# RobotSide.net
KiCad netlist of a schematic drawn in EAGLE
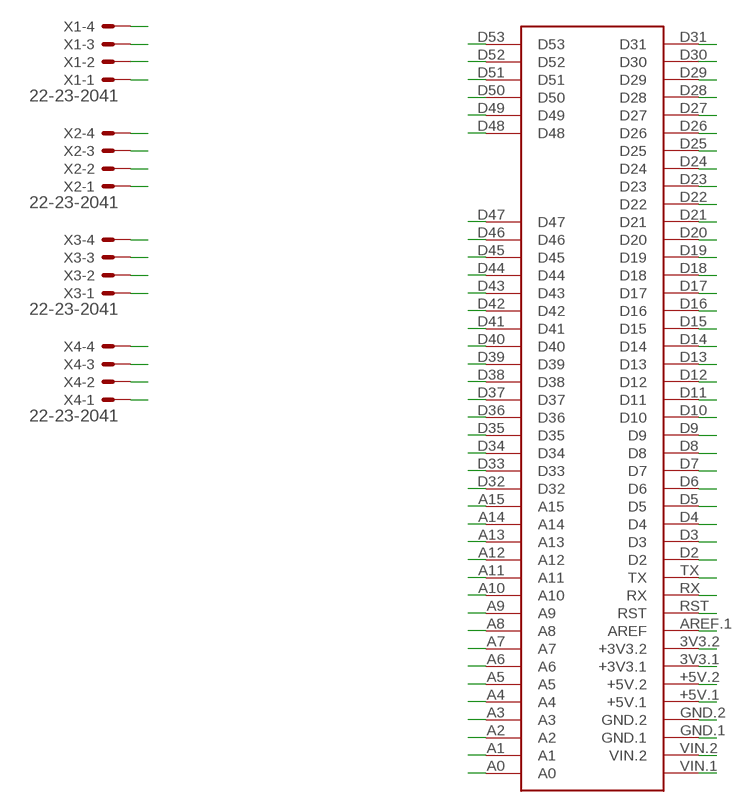
[diagram p0: schematic, sheet 1]
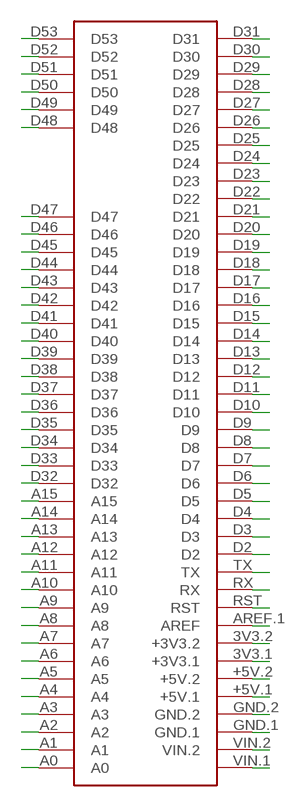
[diagram p1: schematic, sheet 2]

(export (version "E")
  (design (tool "Eeschema 10.0.6"))
  (components
    (comp (ref "U$1")
      (value "MEGA2560_MIKRO")
      (footprint "eagle-import:MEGA2560_MIKRO")
      (libsource (lib "eagle-import") (part "MEGA2560_MIKRO"))
    )
    (comp (ref "X1")
      (value "22-23-2041")
      (footprint "eagle-import:22-23-2041")
      (fields (field (name "MF") "MOLEX"))
      (libsource (lib "eagle-import") (part "22-23-2041"))
    )
    (comp (ref "X2")
      (value "22-23-2041")
      (footprint "eagle-import:22-23-2041")
      (fields (field (name "MF") "MOLEX"))
      (libsource (lib "eagle-import") (part "22-23-2041"))
    )
    (comp (ref "X3")
      (value "22-23-2041")
      (footprint "eagle-import:22-23-2041")
      (fields (field (name "MF") "MOLEX"))
      (libsource (lib "eagle-import") (part "22-23-2041"))
    )
    (comp (ref "X4")
      (value "22-23-2041")
      (footprint "eagle-import:22-23-2041")
      (fields (field (name "MF") "MOLEX"))
      (libsource (lib "eagle-import") (part "22-23-2041"))
    )
    (comp (ref "U$2")
      (value "MEGA2560_MIKRO")
      (footprint "eagle-import:MEGA2560_MIKRO")
      (libsource (lib "eagle-import") (part "MEGA2560_MIKRO"))
    )
  )
  (nets
    (net (code "1") (name "3V3") (class "Default")
      (node (ref "U$1") (pin "3V3.1") (pinfunction "+3V3.1_3V3.1") (pintype "bidirectional"))
      (node (ref "U$1") (pin "3V3.2") (pinfunction "+3V3.2_3V3.2") (pintype "bidirectional"))
    )
    (net (code "2") (name "3V3_A") (class "Default")
      (node (ref "U$2") (pin "3V3.1") (pinfunction "+3V3.1_3V3.1") (pintype "bidirectional"))
      (node (ref "U$2") (pin "3V3.2") (pinfunction "+3V3.2_3V3.2") (pintype "bidirectional"))
    )
    (net (code "3") (name "5V") (class "Default")
      (node (ref "U$1") (pin "+5V.1") (pinfunction "+5V.1_+5V.1") (pintype "bidirectional"))
      (node (ref "U$1") (pin "+5V.2") (pinfunction "+5V.2_+5V.2") (pintype "bidirectional"))
      (node (ref "U$2") (pin "+5V.1") (pinfunction "+5V.1_+5V.1") (pintype "bidirectional"))
      (node (ref "U$2") (pin "+5V.2") (pinfunction "+5V.2_+5V.2") (pintype "bidirectional"))
    )
    (net (code "4") (name "GND") (class "Default")
      (node (ref "U$1") (pin "GND.1") (pinfunction "GND.1_GND.1") (pintype "bidirectional"))
      (node (ref "U$1") (pin "GND.2") (pinfunction "GND.2_GND.2") (pintype "bidirectional"))
      (node (ref "U$2") (pin "GND.1") (pinfunction "GND.1_GND.1") (pintype "bidirectional"))
      (node (ref "U$2") (pin "GND.2") (pinfunction "GND.2_GND.2") (pintype "bidirectional"))
    )
    (net (code "5") (name "VIN") (class "Default")
      (node (ref "U$1") (pin "VIN.1") (pinfunction "VIN.1_VIN.1") (pintype "bidirectional"))
      (node (ref "U$1") (pin "VIN.2") (pinfunction "VIN.2_VIN.2") (pintype "bidirectional"))
    )
    (net (code "6") (name "VIN_A") (class "Default")
      (node (ref "U$2") (pin "VIN.1") (pinfunction "VIN.1_VIN.1") (pintype "bidirectional"))
      (node (ref "U$2") (pin "VIN.2") (pinfunction "VIN.2_VIN.2") (pintype "bidirectional"))
    )
    (net (code "7") (name "unconnected-(U$1-AREF-PadAREF.1)") (class "Default")
      (node (ref "U$1") (pin "AREF.1") (pinfunction "AREF_AREF.1") (pintype "bidirectional"))
    )
    (net (code "8") (name "unconnected-(U$1-PadA0)") (class "Default")
      (node (ref "U$1") (pin "A0") (pinfunction "A0_A0") (pintype "bidirectional"))
    )
    (net (code "9") (name "unconnected-(U$1-PadA1)") (class "Default")
      (node (ref "U$1") (pin "A1") (pinfunction "A1_A1") (pintype "bidirectional"))
    )
    (net (code "10") (name "unconnected-(U$1-PadA2)") (class "Default")
      (node (ref "U$1") (pin "A2") (pinfunction "A2_A2") (pintype "bidirectional"))
    )
    (net (code "11") (name "unconnected-(U$1-PadA3)") (class "Default")
      (node (ref "U$1") (pin "A3") (pinfunction "A3_A3") (pintype "bidirectional"))
    )
    (net (code "12") (name "unconnected-(U$1-PadA4)") (class "Default")
      (node (ref "U$1") (pin "A4") (pinfunction "A4_A4") (pintype "bidirectional"))
    )
    (net (code "13") (name "unconnected-(U$1-PadA5)") (class "Default")
      (node (ref "U$1") (pin "A5") (pinfunction "A5_A5") (pintype "bidirectional"))
    )
    (net (code "14") (name "unconnected-(U$1-PadA6)") (class "Default")
      (node (ref "U$1") (pin "A6") (pinfunction "A6_A6") (pintype "bidirectional"))
    )
    (net (code "15") (name "unconnected-(U$1-PadA7)") (class "Default")
      (node (ref "U$1") (pin "A7") (pinfunction "A7_A7") (pintype "bidirectional"))
    )
    (net (code "16") (name "unconnected-(U$1-PadA8)") (class "Default")
      (node (ref "U$1") (pin "A8") (pinfunction "A8_A8") (pintype "bidirectional"))
    )
    (net (code "17") (name "unconnected-(U$1-PadA9)") (class "Default")
      (node (ref "U$1") (pin "A9") (pinfunction "A9_A9") (pintype "bidirectional"))
    )
    (net (code "18") (name "unconnected-(U$1-PadA10)") (class "Default")
      (node (ref "U$1") (pin "A10") (pinfunction "A10_A10") (pintype "bidirectional"))
    )
    (net (code "19") (name "unconnected-(U$1-PadA11)") (class "Default")
      (node (ref "U$1") (pin "A11") (pinfunction "A11_A11") (pintype "bidirectional"))
    )
    (net (code "20") (name "unconnected-(U$1-PadA12)") (class "Default")
      (node (ref "U$1") (pin "A12") (pinfunction "A12_A12") (pintype "bidirectional"))
    )
    (net (code "21") (name "unconnected-(U$1-PadA13)") (class "Default")
      (node (ref "U$1") (pin "A13") (pinfunction "A13_A13") (pintype "bidirectional"))
    )
    (net (code "22") (name "unconnected-(U$1-PadA14)") (class "Default")
      (node (ref "U$1") (pin "A14") (pinfunction "A14_A14") (pintype "bidirectional"))
    )
    (net (code "23") (name "unconnected-(U$1-PadA15)") (class "Default")
      (node (ref "U$1") (pin "A15") (pinfunction "A15_A15") (pintype "bidirectional"))
    )
    (net (code "24") (name "unconnected-(U$1-PadD2)") (class "Default")
      (node (ref "U$1") (pin "D2") (pinfunction "D2_D2") (pintype "bidirectional"))
    )
    (net (code "25") (name "unconnected-(U$1-PadD3)") (class "Default")
      (node (ref "U$1") (pin "D3") (pinfunction "D3_D3") (pintype "bidirectional"))
    )
    (net (code "26") (name "unconnected-(U$1-PadD4)") (class "Default")
      (node (ref "U$1") (pin "D4") (pinfunction "D4_D4") (pintype "bidirectional"))
    )
    (net (code "27") (name "unconnected-(U$1-PadD5)") (class "Default")
      (node (ref "U$1") (pin "D5") (pinfunction "D5_D5") (pintype "bidirectional"))
    )
    (net (code "28") (name "unconnected-(U$1-PadD6)") (class "Default")
      (node (ref "U$1") (pin "D6") (pinfunction "D6_D6") (pintype "bidirectional"))
    )
    (net (code "29") (name "unconnected-(U$1-PadD7)") (class "Default")
      (node (ref "U$1") (pin "D7") (pinfunction "D7_D7") (pintype "bidirectional"))
    )
    (net (code "30") (name "unconnected-(U$1-PadD8)") (class "Default")
      (node (ref "U$1") (pin "D8") (pinfunction "D8_D8") (pintype "bidirectional"))
    )
    (net (code "31") (name "unconnected-(U$1-PadD9)") (class "Default")
      (node (ref "U$1") (pin "D9") (pinfunction "D9_D9") (pintype "bidirectional"))
    )
    (net (code "32") (name "unconnected-(U$1-PadD10)") (class "Default")
      (node (ref "U$1") (pin "D10") (pinfunction "D10_D10") (pintype "bidirectional"))
    )
    (net (code "33") (name "unconnected-(U$1-PadD11)") (class "Default")
      (node (ref "U$1") (pin "D11") (pinfunction "D11_D11") (pintype "bidirectional"))
    )
    (net (code "34") (name "unconnected-(U$1-PadD12)") (class "Default")
      (node (ref "U$1") (pin "D12") (pinfunction "D12_D12") (pintype "bidirectional"))
    )
    (net (code "35") (name "unconnected-(U$1-PadD13)") (class "Default")
      (node (ref "U$1") (pin "D13") (pinfunction "D13_D13") (pintype "bidirectional"))
    )
    (net (code "36") (name "unconnected-(U$1-PadD14)") (class "Default")
      (node (ref "U$1") (pin "D14") (pinfunction "D14_D14") (pintype "bidirectional"))
    )
    (net (code "37") (name "unconnected-(U$1-PadD15)") (class "Default")
      (node (ref "U$1") (pin "D15") (pinfunction "D15_D15") (pintype "bidirectional"))
    )
    (net (code "38") (name "unconnected-(U$1-PadD16)") (class "Default")
      (node (ref "U$1") (pin "D16") (pinfunction "D16_D16") (pintype "bidirectional"))
    )
    (net (code "39") (name "unconnected-(U$1-PadD17)") (class "Default")
      (node (ref "U$1") (pin "D17") (pinfunction "D17_D17") (pintype "bidirectional"))
    )
    (net (code "40") (name "unconnected-(U$1-PadD18)") (class "Default")
      (node (ref "U$1") (pin "D18") (pinfunction "D18_D18") (pintype "bidirectional"))
    )
    (net (code "41") (name "unconnected-(U$1-PadD19)") (class "Default")
      (node (ref "U$1") (pin "D19") (pinfunction "D19_D19") (pintype "bidirectional"))
    )
    (net (code "42") (name "unconnected-(U$1-PadD20)") (class "Default")
      (node (ref "U$1") (pin "D20") (pinfunction "D20_D20") (pintype "bidirectional"))
    )
    (net (code "43") (name "unconnected-(U$1-PadD21)") (class "Default")
      (node (ref "U$1") (pin "D21") (pinfunction "D21_D21") (pintype "bidirectional"))
    )
    (net (code "44") (name "unconnected-(U$1-PadD22)") (class "Default")
      (node (ref "U$1") (pin "D22") (pinfunction "D22_D22") (pintype "bidirectional"))
    )
    (net (code "45") (name "unconnected-(U$1-PadD23)") (class "Default")
      (node (ref "U$1") (pin "D23") (pinfunction "D23_D23") (pintype "bidirectional"))
    )
    (net (code "46") (name "unconnected-(U$1-PadD24)") (class "Default")
      (node (ref "U$1") (pin "D24") (pinfunction "D24_D24") (pintype "bidirectional"))
    )
    (net (code "47") (name "unconnected-(U$1-PadD25)") (class "Default")
      (node (ref "U$1") (pin "D25") (pinfunction "D25_D25") (pintype "bidirectional"))
    )
    (net (code "48") (name "unconnected-(U$1-PadD26)") (class "Default")
      (node (ref "U$1") (pin "D26") (pinfunction "D26_D26") (pintype "bidirectional"))
    )
    (net (code "49") (name "unconnected-(U$1-PadD27)") (class "Default")
      (node (ref "U$1") (pin "D27") (pinfunction "D27_D27") (pintype "bidirectional"))
    )
    (net (code "50") (name "unconnected-(U$1-PadD28)") (class "Default")
      (node (ref "U$1") (pin "D28") (pinfunction "D28_D28") (pintype "bidirectional"))
    )
    (net (code "51") (name "unconnected-(U$1-PadD29)") (class "Default")
      (node (ref "U$1") (pin "D29") (pinfunction "D29_D29") (pintype "bidirectional"))
    )
    (net (code "52") (name "unconnected-(U$1-PadD30)") (class "Default")
      (node (ref "U$1") (pin "D30") (pinfunction "D30_D30") (pintype "bidirectional"))
    )
    (net (code "53") (name "unconnected-(U$1-PadD31)") (class "Default")
      (node (ref "U$1") (pin "D31") (pinfunction "D31_D31") (pintype "bidirectional"))
    )
    (net (code "54") (name "unconnected-(U$1-PadD32)") (class "Default")
      (node (ref "U$1") (pin "D32") (pinfunction "D32_D32") (pintype "bidirectional"))
    )
    (net (code "55") (name "unconnected-(U$1-PadD33)") (class "Default")
      (node (ref "U$1") (pin "D33") (pinfunction "D33_D33") (pintype "bidirectional"))
    )
    (net (code "56") (name "unconnected-(U$1-PadD34)") (class "Default")
      (node (ref "U$1") (pin "D34") (pinfunction "D34_D34") (pintype "bidirectional"))
    )
    (net (code "57") (name "unconnected-(U$1-PadD35)") (class "Default")
      (node (ref "U$1") (pin "D35") (pinfunction "D35_D35") (pintype "bidirectional"))
    )
    (net (code "58") (name "unconnected-(U$1-PadD36)") (class "Default")
      (node (ref "U$1") (pin "D36") (pinfunction "D36_D36") (pintype "bidirectional"))
    )
    (net (code "59") (name "unconnected-(U$1-PadD37)") (class "Default")
      (node (ref "U$1") (pin "D37") (pinfunction "D37_D37") (pintype "bidirectional"))
    )
    (net (code "60") (name "unconnected-(U$1-PadD38)") (class "Default")
      (node (ref "U$1") (pin "D38") (pinfunction "D38_D38") (pintype "bidirectional"))
    )
    (net (code "61") (name "unconnected-(U$1-PadD39)") (class "Default")
      (node (ref "U$1") (pin "D39") (pinfunction "D39_D39") (pintype "bidirectional"))
    )
    (net (code "62") (name "unconnected-(U$1-PadD40)") (class "Default")
      (node (ref "U$1") (pin "D40") (pinfunction "D40_D40") (pintype "bidirectional"))
    )
    (net (code "63") (name "unconnected-(U$1-PadD41)") (class "Default")
      (node (ref "U$1") (pin "D41") (pinfunction "D41_D41") (pintype "bidirectional"))
    )
    (net (code "64") (name "unconnected-(U$1-PadD42)") (class "Default")
      (node (ref "U$1") (pin "D42") (pinfunction "D42_D42") (pintype "bidirectional"))
    )
    (net (code "65") (name "unconnected-(U$1-PadD43)") (class "Default")
      (node (ref "U$1") (pin "D43") (pinfunction "D43_D43") (pintype "bidirectional"))
    )
    (net (code "66") (name "unconnected-(U$1-PadD44)") (class "Default")
      (node (ref "U$1") (pin "D44") (pinfunction "D44_D44") (pintype "bidirectional"))
    )
    (net (code "67") (name "unconnected-(U$1-PadD45)") (class "Default")
      (node (ref "U$1") (pin "D45") (pinfunction "D45_D45") (pintype "bidirectional"))
    )
    (net (code "68") (name "unconnected-(U$1-PadD46)") (class "Default")
      (node (ref "U$1") (pin "D46") (pinfunction "D46_D46") (pintype "bidirectional"))
    )
    (net (code "69") (name "unconnected-(U$1-PadD47)") (class "Default")
      (node (ref "U$1") (pin "D47") (pinfunction "D47_D47") (pintype "bidirectional"))
    )
    (net (code "70") (name "unconnected-(U$1-PadD48)") (class "Default")
      (node (ref "U$1") (pin "D48") (pinfunction "D48_D48") (pintype "bidirectional"))
    )
    (net (code "71") (name "unconnected-(U$1-PadD49)") (class "Default")
      (node (ref "U$1") (pin "D49") (pinfunction "D49_D49") (pintype "bidirectional"))
    )
    (net (code "72") (name "unconnected-(U$1-PadD50)") (class "Default")
      (node (ref "U$1") (pin "D50") (pinfunction "D50_D50") (pintype "bidirectional"))
    )
    (net (code "73") (name "unconnected-(U$1-PadD51)") (class "Default")
      (node (ref "U$1") (pin "D51") (pinfunction "D51_D51") (pintype "bidirectional"))
    )
    (net (code "74") (name "unconnected-(U$1-PadD52)") (class "Default")
      (node (ref "U$1") (pin "D52") (pinfunction "D52_D52") (pintype "bidirectional"))
    )
    (net (code "75") (name "unconnected-(U$1-PadD53)") (class "Default")
      (node (ref "U$1") (pin "D53") (pinfunction "D53_D53") (pintype "bidirectional"))
    )
    (net (code "76") (name "unconnected-(U$1-PadRST)") (class "Default")
      (node (ref "U$1") (pin "RST") (pinfunction "RST_RST") (pintype "bidirectional"))
    )
    (net (code "77") (name "unconnected-(U$1-PadRX)") (class "Default")
      (node (ref "U$1") (pin "RX") (pinfunction "RX_RX") (pintype "bidirectional"))
    )
    (net (code "78") (name "unconnected-(U$1-PadTX)") (class "Default")
      (node (ref "U$1") (pin "TX") (pinfunction "TX_TX") (pintype "bidirectional"))
    )
    (net (code "79") (name "unconnected-(U$2-AREF-PadAREF.1)") (class "Default")
      (node (ref "U$2") (pin "AREF.1") (pinfunction "AREF_AREF.1") (pintype "bidirectional"))
    )
    (net (code "80") (name "unconnected-(U$2-PadA0)") (class "Default")
      (node (ref "U$2") (pin "A0") (pinfunction "A0_A0") (pintype "bidirectional"))
    )
    (net (code "81") (name "unconnected-(U$2-PadA1)") (class "Default")
      (node (ref "U$2") (pin "A1") (pinfunction "A1_A1") (pintype "bidirectional"))
    )
    (net (code "82") (name "unconnected-(U$2-PadA2)") (class "Default")
      (node (ref "U$2") (pin "A2") (pinfunction "A2_A2") (pintype "bidirectional"))
    )
    (net (code "83") (name "unconnected-(U$2-PadA3)") (class "Default")
      (node (ref "U$2") (pin "A3") (pinfunction "A3_A3") (pintype "bidirectional"))
    )
    (net (code "84") (name "unconnected-(U$2-PadA4)") (class "Default")
      (node (ref "U$2") (pin "A4") (pinfunction "A4_A4") (pintype "bidirectional"))
    )
    (net (code "85") (name "unconnected-(U$2-PadA5)") (class "Default")
      (node (ref "U$2") (pin "A5") (pinfunction "A5_A5") (pintype "bidirectional"))
    )
    (net (code "86") (name "unconnected-(U$2-PadA6)") (class "Default")
      (node (ref "U$2") (pin "A6") (pinfunction "A6_A6") (pintype "bidirectional"))
    )
    (net (code "87") (name "unconnected-(U$2-PadA7)") (class "Default")
      (node (ref "U$2") (pin "A7") (pinfunction "A7_A7") (pintype "bidirectional"))
    )
    (net (code "88") (name "unconnected-(U$2-PadA8)") (class "Default")
      (node (ref "U$2") (pin "A8") (pinfunction "A8_A8") (pintype "bidirectional"))
    )
    (net (code "89") (name "unconnected-(U$2-PadA9)") (class "Default")
      (node (ref "U$2") (pin "A9") (pinfunction "A9_A9") (pintype "bidirectional"))
    )
    (net (code "90") (name "unconnected-(U$2-PadA10)") (class "Default")
      (node (ref "U$2") (pin "A10") (pinfunction "A10_A10") (pintype "bidirectional"))
    )
    (net (code "91") (name "unconnected-(U$2-PadA11)") (class "Default")
      (node (ref "U$2") (pin "A11") (pinfunction "A11_A11") (pintype "bidirectional"))
    )
    (net (code "92") (name "unconnected-(U$2-PadA12)") (class "Default")
      (node (ref "U$2") (pin "A12") (pinfunction "A12_A12") (pintype "bidirectional"))
    )
    (net (code "93") (name "unconnected-(U$2-PadA13)") (class "Default")
      (node (ref "U$2") (pin "A13") (pinfunction "A13_A13") (pintype "bidirectional"))
    )
    (net (code "94") (name "unconnected-(U$2-PadA14)") (class "Default")
      (node (ref "U$2") (pin "A14") (pinfunction "A14_A14") (pintype "bidirectional"))
    )
    (net (code "95") (name "unconnected-(U$2-PadA15)") (class "Default")
      (node (ref "U$2") (pin "A15") (pinfunction "A15_A15") (pintype "bidirectional"))
    )
    (net (code "96") (name "unconnected-(U$2-PadD2)") (class "Default")
      (node (ref "U$2") (pin "D2") (pinfunction "D2_D2") (pintype "bidirectional"))
    )
    (net (code "97") (name "unconnected-(U$2-PadD3)") (class "Default")
      (node (ref "U$2") (pin "D3") (pinfunction "D3_D3") (pintype "bidirectional"))
    )
    (net (code "98") (name "unconnected-(U$2-PadD4)") (class "Default")
      (node (ref "U$2") (pin "D4") (pinfunction "D4_D4") (pintype "bidirectional"))
    )
    (net (code "99") (name "unconnected-(U$2-PadD5)") (class "Default")
      (node (ref "U$2") (pin "D5") (pinfunction "D5_D5") (pintype "bidirectional"))
    )
    (net (code "100") (name "unconnected-(U$2-PadD6)") (class "Default")
      (node (ref "U$2") (pin "D6") (pinfunction "D6_D6") (pintype "bidirectional"))
    )
    (net (code "101") (name "unconnected-(U$2-PadD7)") (class "Default")
      (node (ref "U$2") (pin "D7") (pinfunction "D7_D7") (pintype "bidirectional"))
    )
    (net (code "102") (name "unconnected-(U$2-PadD8)") (class "Default")
      (node (ref "U$2") (pin "D8") (pinfunction "D8_D8") (pintype "bidirectional"))
    )
    (net (code "103") (name "unconnected-(U$2-PadD9)") (class "Default")
      (node (ref "U$2") (pin "D9") (pinfunction "D9_D9") (pintype "bidirectional"))
    )
    (net (code "104") (name "unconnected-(U$2-PadD10)") (class "Default")
      (node (ref "U$2") (pin "D10") (pinfunction "D10_D10") (pintype "bidirectional"))
    )
    (net (code "105") (name "unconnected-(U$2-PadD11)") (class "Default")
      (node (ref "U$2") (pin "D11") (pinfunction "D11_D11") (pintype "bidirectional"))
    )
    (net (code "106") (name "unconnected-(U$2-PadD12)") (class "Default")
      (node (ref "U$2") (pin "D12") (pinfunction "D12_D12") (pintype "bidirectional"))
    )
    (net (code "107") (name "unconnected-(U$2-PadD13)") (class "Default")
      (node (ref "U$2") (pin "D13") (pinfunction "D13_D13") (pintype "bidirectional"))
    )
    (net (code "108") (name "unconnected-(U$2-PadD14)") (class "Default")
      (node (ref "U$2") (pin "D14") (pinfunction "D14_D14") (pintype "bidirectional"))
    )
    (net (code "109") (name "unconnected-(U$2-PadD15)") (class "Default")
      (node (ref "U$2") (pin "D15") (pinfunction "D15_D15") (pintype "bidirectional"))
    )
    (net (code "110") (name "unconnected-(U$2-PadD16)") (class "Default")
      (node (ref "U$2") (pin "D16") (pinfunction "D16_D16") (pintype "bidirectional"))
    )
    (net (code "111") (name "unconnected-(U$2-PadD17)") (class "Default")
      (node (ref "U$2") (pin "D17") (pinfunction "D17_D17") (pintype "bidirectional"))
    )
    (net (code "112") (name "unconnected-(U$2-PadD18)") (class "Default")
      (node (ref "U$2") (pin "D18") (pinfunction "D18_D18") (pintype "bidirectional"))
    )
    (net (code "113") (name "unconnected-(U$2-PadD19)") (class "Default")
      (node (ref "U$2") (pin "D19") (pinfunction "D19_D19") (pintype "bidirectional"))
    )
    (net (code "114") (name "unconnected-(U$2-PadD20)") (class "Default")
      (node (ref "U$2") (pin "D20") (pinfunction "D20_D20") (pintype "bidirectional"))
    )
    (net (code "115") (name "unconnected-(U$2-PadD21)") (class "Default")
      (node (ref "U$2") (pin "D21") (pinfunction "D21_D21") (pintype "bidirectional"))
    )
    (net (code "116") (name "unconnected-(U$2-PadD22)") (class "Default")
      (node (ref "U$2") (pin "D22") (pinfunction "D22_D22") (pintype "bidirectional"))
    )
    (net (code "117") (name "unconnected-(U$2-PadD23)") (class "Default")
      (node (ref "U$2") (pin "D23") (pinfunction "D23_D23") (pintype "bidirectional"))
    )
    (net (code "118") (name "unconnected-(U$2-PadD24)") (class "Default")
      (node (ref "U$2") (pin "D24") (pinfunction "D24_D24") (pintype "bidirectional"))
    )
    (net (code "119") (name "unconnected-(U$2-PadD25)") (class "Default")
      (node (ref "U$2") (pin "D25") (pinfunction "D25_D25") (pintype "bidirectional"))
    )
    (net (code "120") (name "unconnected-(U$2-PadD26)") (class "Default")
      (node (ref "U$2") (pin "D26") (pinfunction "D26_D26") (pintype "bidirectional"))
    )
    (net (code "121") (name "unconnected-(U$2-PadD27)") (class "Default")
      (node (ref "U$2") (pin "D27") (pinfunction "D27_D27") (pintype "bidirectional"))
    )
    (net (code "122") (name "unconnected-(U$2-PadD28)") (class "Default")
      (node (ref "U$2") (pin "D28") (pinfunction "D28_D28") (pintype "bidirectional"))
    )
    (net (code "123") (name "unconnected-(U$2-PadD29)") (class "Default")
      (node (ref "U$2") (pin "D29") (pinfunction "D29_D29") (pintype "bidirectional"))
    )
    (net (code "124") (name "unconnected-(U$2-PadD30)") (class "Default")
      (node (ref "U$2") (pin "D30") (pinfunction "D30_D30") (pintype "bidirectional"))
    )
    (net (code "125") (name "unconnected-(U$2-PadD31)") (class "Default")
      (node (ref "U$2") (pin "D31") (pinfunction "D31_D31") (pintype "bidirectional"))
    )
    (net (code "126") (name "unconnected-(U$2-PadD32)") (class "Default")
      (node (ref "U$2") (pin "D32") (pinfunction "D32_D32") (pintype "bidirectional"))
    )
    (net (code "127") (name "unconnected-(U$2-PadD33)") (class "Default")
      (node (ref "U$2") (pin "D33") (pinfunction "D33_D33") (pintype "bidirectional"))
    )
    (net (code "128") (name "unconnected-(U$2-PadD34)") (class "Default")
      (node (ref "U$2") (pin "D34") (pinfunction "D34_D34") (pintype "bidirectional"))
    )
    (net (code "129") (name "unconnected-(U$2-PadD35)") (class "Default")
      (node (ref "U$2") (pin "D35") (pinfunction "D35_D35") (pintype "bidirectional"))
    )
    (net (code "130") (name "unconnected-(U$2-PadD36)") (class "Default")
      (node (ref "U$2") (pin "D36") (pinfunction "D36_D36") (pintype "bidirectional"))
    )
    (net (code "131") (name "unconnected-(U$2-PadD37)") (class "Default")
      (node (ref "U$2") (pin "D37") (pinfunction "D37_D37") (pintype "bidirectional"))
    )
    (net (code "132") (name "unconnected-(U$2-PadD38)") (class "Default")
      (node (ref "U$2") (pin "D38") (pinfunction "D38_D38") (pintype "bidirectional"))
    )
    (net (code "133") (name "unconnected-(U$2-PadD39)") (class "Default")
      (node (ref "U$2") (pin "D39") (pinfunction "D39_D39") (pintype "bidirectional"))
    )
    (net (code "134") (name "unconnected-(U$2-PadD40)") (class "Default")
      (node (ref "U$2") (pin "D40") (pinfunction "D40_D40") (pintype "bidirectional"))
    )
    (net (code "135") (name "unconnected-(U$2-PadD41)") (class "Default")
      (node (ref "U$2") (pin "D41") (pinfunction "D41_D41") (pintype "bidirectional"))
    )
    (net (code "136") (name "unconnected-(U$2-PadD42)") (class "Default")
      (node (ref "U$2") (pin "D42") (pinfunction "D42_D42") (pintype "bidirectional"))
    )
    (net (code "137") (name "unconnected-(U$2-PadD43)") (class "Default")
      (node (ref "U$2") (pin "D43") (pinfunction "D43_D43") (pintype "bidirectional"))
    )
    (net (code "138") (name "unconnected-(U$2-PadD44)") (class "Default")
      (node (ref "U$2") (pin "D44") (pinfunction "D44_D44") (pintype "bidirectional"))
    )
    (net (code "139") (name "unconnected-(U$2-PadD45)") (class "Default")
      (node (ref "U$2") (pin "D45") (pinfunction "D45_D45") (pintype "bidirectional"))
    )
    (net (code "140") (name "unconnected-(U$2-PadD46)") (class "Default")
      (node (ref "U$2") (pin "D46") (pinfunction "D46_D46") (pintype "bidirectional"))
    )
    (net (code "141") (name "unconnected-(U$2-PadD47)") (class "Default")
      (node (ref "U$2") (pin "D47") (pinfunction "D47_D47") (pintype "bidirectional"))
    )
    (net (code "142") (name "unconnected-(U$2-PadD48)") (class "Default")
      (node (ref "U$2") (pin "D48") (pinfunction "D48_D48") (pintype "bidirectional"))
    )
    (net (code "143") (name "unconnected-(U$2-PadD49)") (class "Default")
      (node (ref "U$2") (pin "D49") (pinfunction "D49_D49") (pintype "bidirectional"))
    )
    (net (code "144") (name "unconnected-(U$2-PadD50)") (class "Default")
      (node (ref "U$2") (pin "D50") (pinfunction "D50_D50") (pintype "bidirectional"))
    )
    (net (code "145") (name "unconnected-(U$2-PadD51)") (class "Default")
      (node (ref "U$2") (pin "D51") (pinfunction "D51_D51") (pintype "bidirectional"))
    )
    (net (code "146") (name "unconnected-(U$2-PadD52)") (class "Default")
      (node (ref "U$2") (pin "D52") (pinfunction "D52_D52") (pintype "bidirectional"))
    )
    (net (code "147") (name "unconnected-(U$2-PadD53)") (class "Default")
      (node (ref "U$2") (pin "D53") (pinfunction "D53_D53") (pintype "bidirectional"))
    )
    (net (code "148") (name "unconnected-(U$2-PadRST)") (class "Default")
      (node (ref "U$2") (pin "RST") (pinfunction "RST_RST") (pintype "bidirectional"))
    )
    (net (code "149") (name "unconnected-(U$2-PadRX)") (class "Default")
      (node (ref "U$2") (pin "RX") (pinfunction "RX_RX") (pintype "bidirectional"))
    )
    (net (code "150") (name "unconnected-(U$2-PadTX)") (class "Default")
      (node (ref "U$2") (pin "TX") (pinfunction "TX_TX") (pintype "bidirectional"))
    )
    (net (code "151") (name "unconnected-(X1A-S-Pad1)") (class "Default")
      (node (ref "X1") (pin "1") (pinfunction "S_1") (pintype "passive"))
    )
    (net (code "152") (name "unconnected-(X1B-S-Pad2)") (class "Default")
      (node (ref "X1") (pin "2") (pinfunction "S_2") (pintype "passive"))
    )
    (net (code "153") (name "unconnected-(X1C-S-Pad3)") (class "Default")
      (node (ref "X1") (pin "3") (pinfunction "S_3") (pintype "passive"))
    )
    (net (code "154") (name "unconnected-(X1D-S-Pad4)") (class "Default")
      (node (ref "X1") (pin "4") (pinfunction "S_4") (pintype "passive"))
    )
    (net (code "155") (name "unconnected-(X2A-S-Pad1)") (class "Default")
      (node (ref "X2") (pin "1") (pinfunction "S_1") (pintype "passive"))
    )
    (net (code "156") (name "unconnected-(X2B-S-Pad2)") (class "Default")
      (node (ref "X2") (pin "2") (pinfunction "S_2") (pintype "passive"))
    )
    (net (code "157") (name "unconnected-(X2C-S-Pad3)") (class "Default")
      (node (ref "X2") (pin "3") (pinfunction "S_3") (pintype "passive"))
    )
    (net (code "158") (name "unconnected-(X2D-S-Pad4)") (class "Default")
      (node (ref "X2") (pin "4") (pinfunction "S_4") (pintype "passive"))
    )
    (net (code "159") (name "unconnected-(X3A-S-Pad1)") (class "Default")
      (node (ref "X3") (pin "1") (pinfunction "S_1") (pintype "passive"))
    )
    (net (code "160") (name "unconnected-(X3B-S-Pad2)") (class "Default")
      (node (ref "X3") (pin "2") (pinfunction "S_2") (pintype "passive"))
    )
    (net (code "161") (name "unconnected-(X3C-S-Pad3)") (class "Default")
      (node (ref "X3") (pin "3") (pinfunction "S_3") (pintype "passive"))
    )
    (net (code "162") (name "unconnected-(X3D-S-Pad4)") (class "Default")
      (node (ref "X3") (pin "4") (pinfunction "S_4") (pintype "passive"))
    )
    (net (code "163") (name "unconnected-(X4A-S-Pad1)") (class "Default")
      (node (ref "X4") (pin "1") (pinfunction "S_1") (pintype "passive"))
    )
    (net (code "164") (name "unconnected-(X4B-S-Pad2)") (class "Default")
      (node (ref "X4") (pin "2") (pinfunction "S_2") (pintype "passive"))
    )
    (net (code "165") (name "unconnected-(X4C-S-Pad3)") (class "Default")
      (node (ref "X4") (pin "3") (pinfunction "S_3") (pintype "passive"))
    )
    (net (code "166") (name "unconnected-(X4D-S-Pad4)") (class "Default")
      (node (ref "X4") (pin "4") (pinfunction "S_4") (pintype "passive"))
    )
  )
)
